# COBConnector.net
KiCad netlist of a schematic drawn in Altium Designer
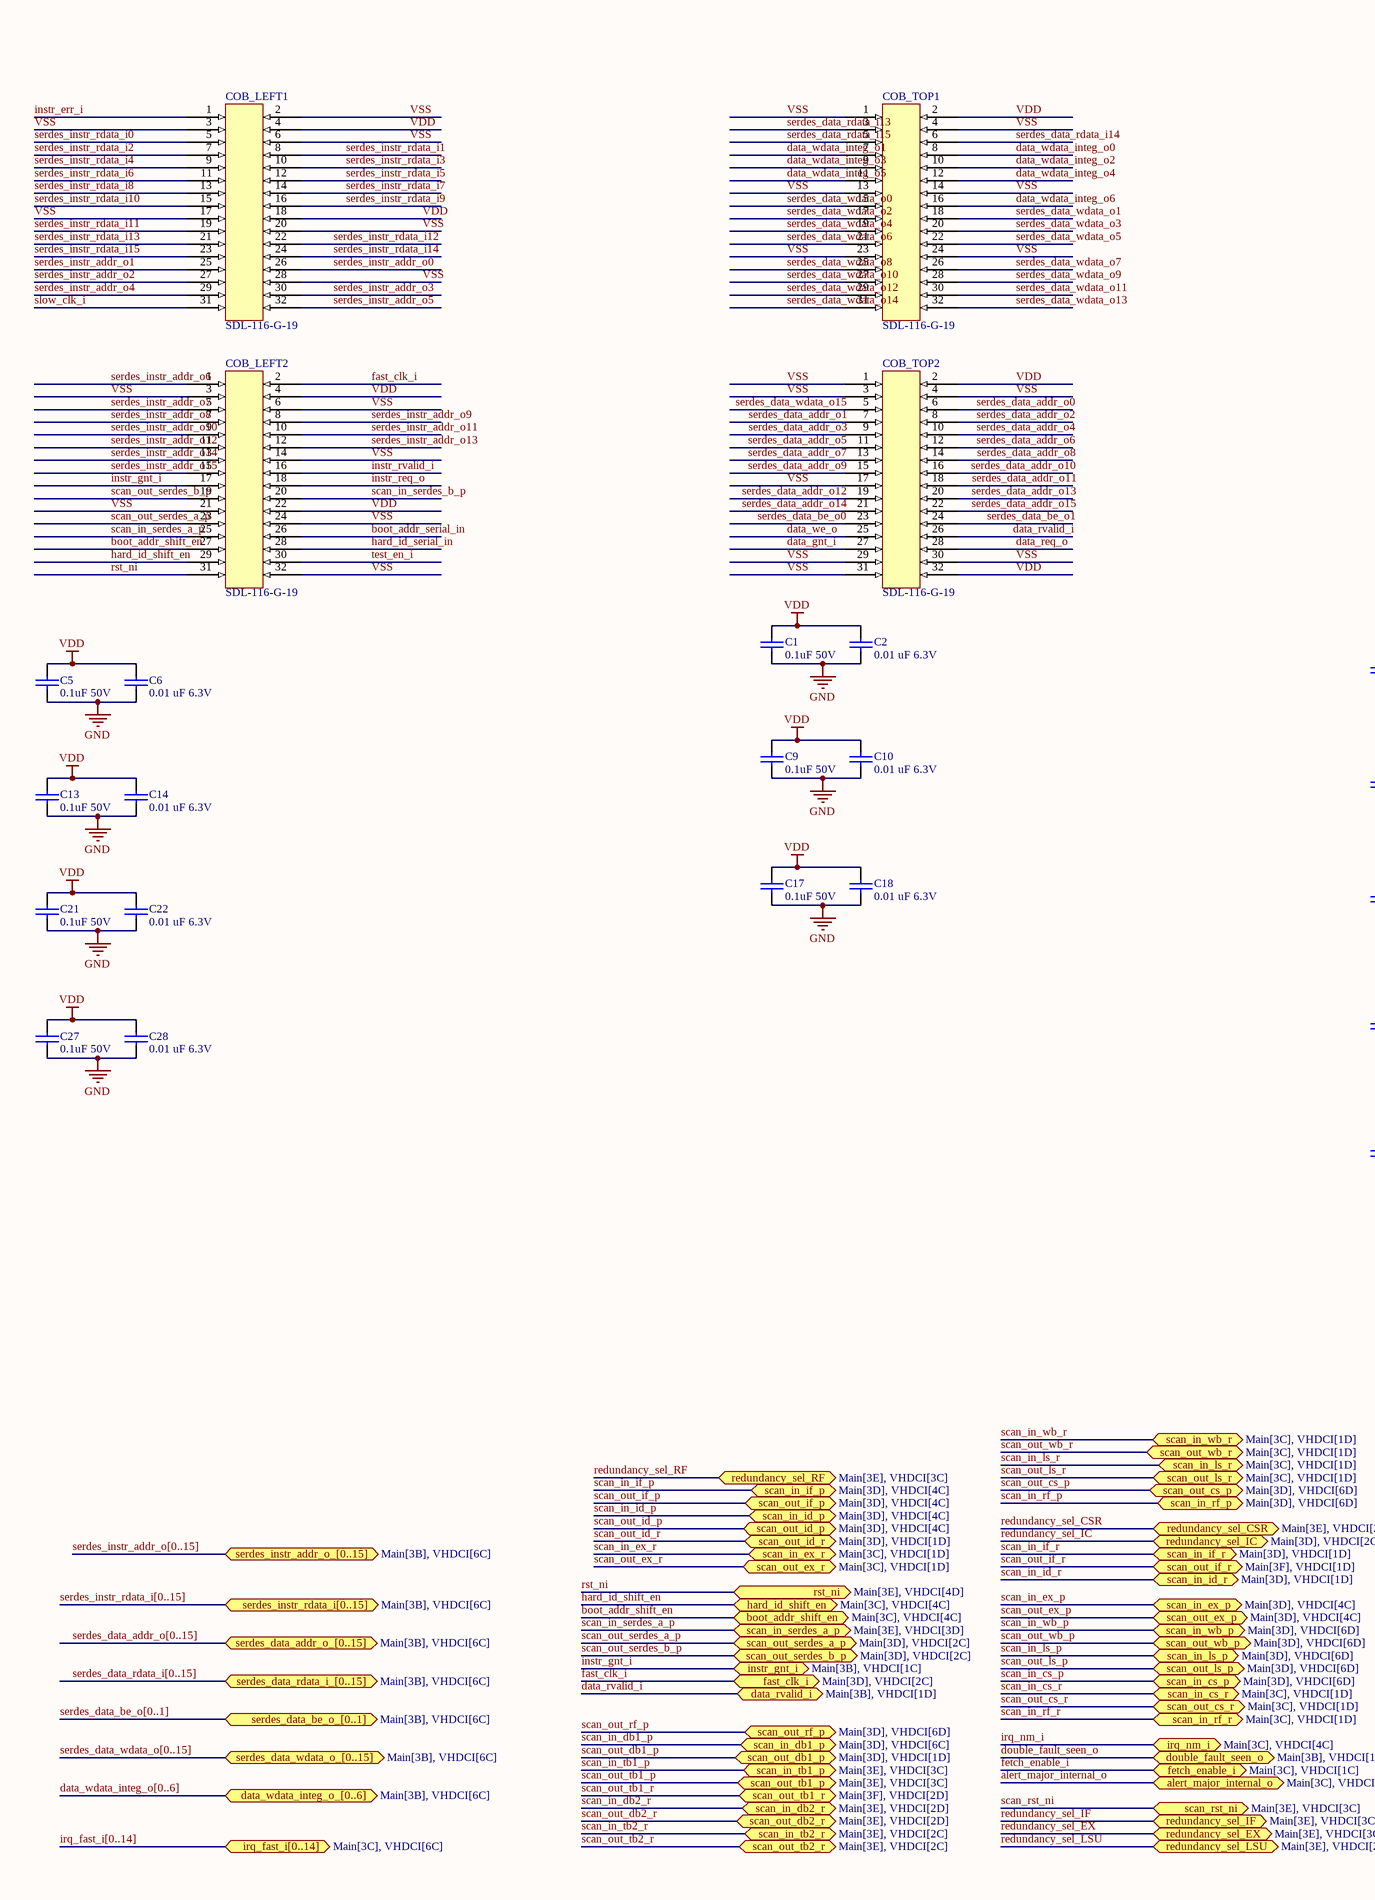
[diagram p0: COBConnector.SchDoc, left]
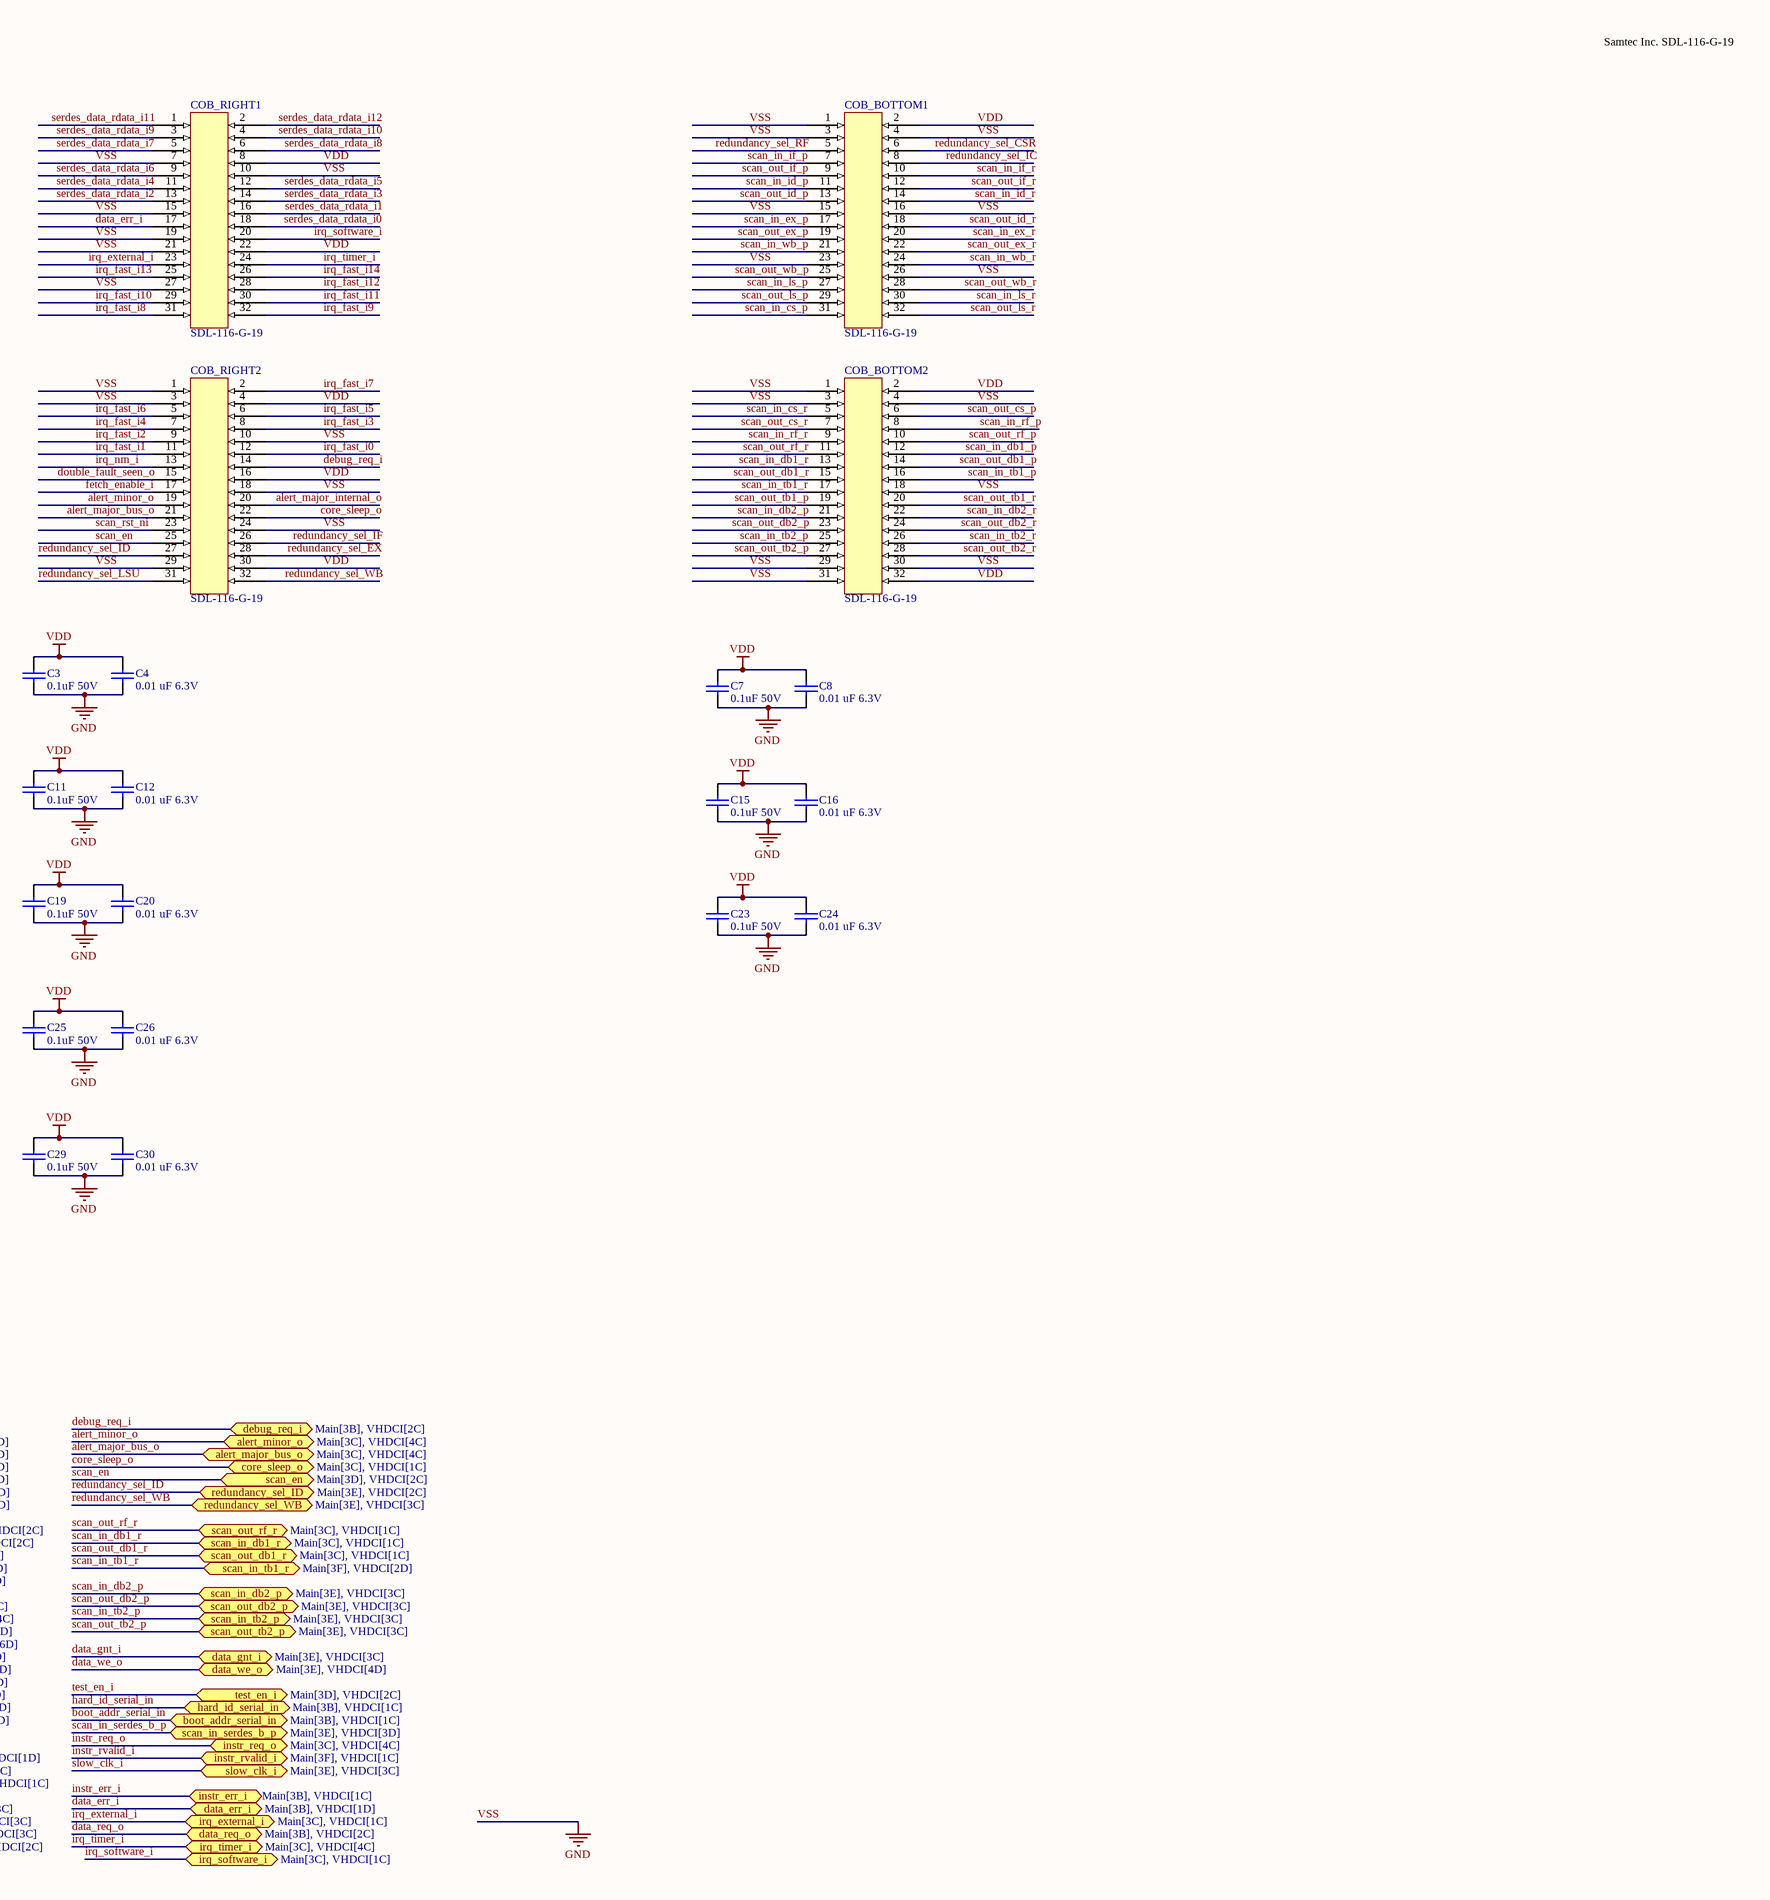
[diagram p1: COBConnector.SchDoc, right]

(export (version "E")
  (design (tool "Eeschema 10.0.6"))
  (components
    (comp (ref "C1")
      (value "0.1uF 50V")
      (footprint "C0603-XXXXXX-XXX")
      (description "0.1 µF ±20% 50V Ceramic Capacitor X7R 0603")
      (libsource (lib "00-100001-001") (part "C0603C104M5RAC7867"))
    )
    (comp (ref "C2")
      (value "0.01 uF 6.3V")
      (footprint "C0603-XXXXXX-XXX")
      (description "Multilayer Ceramic Capacitors MLCC - SMD/SMT 6.3V 0.01uF X7R 0603 20%")
      (libsource (lib "00-100001-001") (part "C0603F103M9RACTU"))
    )
    (comp (ref "C3")
      (value "0.1uF 50V")
      (footprint "C0603-XXXXXX-XXX")
      (description "0.1 µF ±20% 50V Ceramic Capacitor X7R 0603")
      (libsource (lib "00-100001-001") (part "C0603C104M5RAC7867"))
    )
    (comp (ref "C4")
      (value "0.01 uF 6.3V")
      (footprint "C0603-XXXXXX-XXX")
      (description "Multilayer Ceramic Capacitors MLCC - SMD/SMT 6.3V 0.01uF X7R 0603 20%")
      (libsource (lib "00-100001-001") (part "C0603F103M9RACTU"))
    )
    (comp (ref "C5")
      (value "0.1uF 50V")
      (footprint "C0603-XXXXXX-XXX")
      (description "0.1 µF ±20% 50V Ceramic Capacitor X7R 0603")
      (libsource (lib "00-100001-001") (part "C0603C104M5RAC7867"))
    )
    (comp (ref "C6")
      (value "0.01 uF 6.3V")
      (footprint "C0603-XXXXXX-XXX")
      (description "Multilayer Ceramic Capacitors MLCC - SMD/SMT 6.3V 0.01uF X7R 0603 20%")
      (libsource (lib "00-100001-001") (part "C0603F103M9RACTU"))
    )
    (comp (ref "C7")
      (value "0.1uF 50V")
      (footprint "C0603-XXXXXX-XXX")
      (description "0.1 µF ±20% 50V Ceramic Capacitor X7R 0603")
      (libsource (lib "00-100001-001") (part "C0603C104M5RAC7867"))
    )
    (comp (ref "C8")
      (value "0.01 uF 6.3V")
      (footprint "C0603-XXXXXX-XXX")
      (description "Multilayer Ceramic Capacitors MLCC - SMD/SMT 6.3V 0.01uF X7R 0603 20%")
      (libsource (lib "00-100001-001") (part "C0603F103M9RACTU"))
    )
    (comp (ref "C9")
      (value "0.1uF 50V")
      (footprint "C0603-XXXXXX-XXX")
      (description "0.1 µF ±20% 50V Ceramic Capacitor X7R 0603")
      (libsource (lib "00-100001-001") (part "C0603C104M5RAC7867"))
    )
    (comp (ref "C10")
      (value "0.01 uF 6.3V")
      (footprint "C0603-XXXXXX-XXX")
      (description "Multilayer Ceramic Capacitors MLCC - SMD/SMT 6.3V 0.01uF X7R 0603 20%")
      (libsource (lib "00-100001-001") (part "C0603F103M9RACTU"))
    )
    (comp (ref "C11")
      (value "0.1uF 50V")
      (footprint "C0603-XXXXXX-XXX")
      (description "0.1 µF ±20% 50V Ceramic Capacitor X7R 0603")
      (libsource (lib "00-100001-001") (part "C0603C104M5RAC7867"))
    )
    (comp (ref "C12")
      (value "0.01 uF 6.3V")
      (footprint "C0603-XXXXXX-XXX")
      (description "Multilayer Ceramic Capacitors MLCC - SMD/SMT 6.3V 0.01uF X7R 0603 20%")
      (libsource (lib "00-100001-001") (part "C0603F103M9RACTU"))
    )
    (comp (ref "C13")
      (value "0.1uF 50V")
      (footprint "C0603-XXXXXX-XXX")
      (description "0.1 µF ±20% 50V Ceramic Capacitor X7R 0603")
      (libsource (lib "00-100001-001") (part "C0603C104M5RAC7867"))
    )
    (comp (ref "C14")
      (value "0.01 uF 6.3V")
      (footprint "C0603-XXXXXX-XXX")
      (description "Multilayer Ceramic Capacitors MLCC - SMD/SMT 6.3V 0.01uF X7R 0603 20%")
      (libsource (lib "00-100001-001") (part "C0603F103M9RACTU"))
    )
    (comp (ref "C15")
      (value "0.1uF 50V")
      (footprint "C0603-XXXXXX-XXX")
      (description "0.1 µF ±20% 50V Ceramic Capacitor X7R 0603")
      (libsource (lib "00-100001-001") (part "C0603C104M5RAC7867"))
    )
    (comp (ref "C16")
      (value "0.01 uF 6.3V")
      (footprint "C0603-XXXXXX-XXX")
      (description "Multilayer Ceramic Capacitors MLCC - SMD/SMT 6.3V 0.01uF X7R 0603 20%")
      (libsource (lib "00-100001-001") (part "C0603F103M9RACTU"))
    )
    (comp (ref "C17")
      (value "0.1uF 50V")
      (footprint "C0603-XXXXXX-XXX")
      (description "0.1 µF ±20% 50V Ceramic Capacitor X7R 0603")
      (libsource (lib "00-100001-001") (part "C0603C104M5RAC7867"))
    )
    (comp (ref "C18")
      (value "0.01 uF 6.3V")
      (footprint "C0603-XXXXXX-XXX")
      (description "Multilayer Ceramic Capacitors MLCC - SMD/SMT 6.3V 0.01uF X7R 0603 20%")
      (libsource (lib "00-100001-001") (part "C0603F103M9RACTU"))
    )
    (comp (ref "C19")
      (value "0.1uF 50V")
      (footprint "C0603-XXXXXX-XXX")
      (description "0.1 µF ±20% 50V Ceramic Capacitor X7R 0603")
      (libsource (lib "00-100001-001") (part "C0603C104M5RAC7867"))
    )
    (comp (ref "C20")
      (value "0.01 uF 6.3V")
      (footprint "C0603-XXXXXX-XXX")
      (description "Multilayer Ceramic Capacitors MLCC - SMD/SMT 6.3V 0.01uF X7R 0603 20%")
      (libsource (lib "00-100001-001") (part "C0603F103M9RACTU"))
    )
    (comp (ref "C21")
      (value "0.1uF 50V")
      (footprint "C0603-XXXXXX-XXX")
      (description "0.1 µF ±20% 50V Ceramic Capacitor X7R 0603")
      (libsource (lib "00-100001-001") (part "C0603C104M5RAC7867"))
    )
    (comp (ref "C22")
      (value "0.01 uF 6.3V")
      (footprint "C0603-XXXXXX-XXX")
      (description "Multilayer Ceramic Capacitors MLCC - SMD/SMT 6.3V 0.01uF X7R 0603 20%")
      (libsource (lib "00-100001-001") (part "C0603F103M9RACTU"))
    )
    (comp (ref "C23")
      (value "0.1uF 50V")
      (footprint "C0603-XXXXXX-XXX")
      (description "0.1 µF ±20% 50V Ceramic Capacitor X7R 0603")
      (libsource (lib "00-100001-001") (part "C0603C104M5RAC7867"))
    )
    (comp (ref "C24")
      (value "0.01 uF 6.3V")
      (footprint "C0603-XXXXXX-XXX")
      (description "Multilayer Ceramic Capacitors MLCC - SMD/SMT 6.3V 0.01uF X7R 0603 20%")
      (libsource (lib "00-100001-001") (part "C0603F103M9RACTU"))
    )
    (comp (ref "C25")
      (value "0.1uF 50V")
      (footprint "C0603-XXXXXX-XXX")
      (description "0.1 µF ±20% 50V Ceramic Capacitor X7R 0603")
      (libsource (lib "00-100001-001") (part "C0603C104M5RAC7867"))
    )
    (comp (ref "C26")
      (value "0.01 uF 6.3V")
      (footprint "C0603-XXXXXX-XXX")
      (description "Multilayer Ceramic Capacitors MLCC - SMD/SMT 6.3V 0.01uF X7R 0603 20%")
      (libsource (lib "00-100001-001") (part "C0603F103M9RACTU"))
    )
    (comp (ref "C27")
      (value "0.1uF 50V")
      (footprint "C0603-XXXXXX-XXX")
      (description "0.1 µF ±20% 50V Ceramic Capacitor X7R 0603")
      (libsource (lib "00-100001-001") (part "C0603C104M5RAC7867"))
    )
    (comp (ref "C28")
      (value "0.01 uF 6.3V")
      (footprint "C0603-XXXXXX-XXX")
      (description "Multilayer Ceramic Capacitors MLCC - SMD/SMT 6.3V 0.01uF X7R 0603 20%")
      (libsource (lib "00-100001-001") (part "C0603F103M9RACTU"))
    )
    (comp (ref "C29")
      (value "0.1uF 50V")
      (footprint "C0603-XXXXXX-XXX")
      (description "0.1 µF ±20% 50V Ceramic Capacitor X7R 0603")
      (libsource (lib "00-100001-001") (part "C0603C104M5RAC7867"))
    )
    (comp (ref "C30")
      (value "0.01 uF 6.3V")
      (footprint "C0603-XXXXXX-XXX")
      (description "Multilayer Ceramic Capacitors MLCC - SMD/SMT 6.3V 0.01uF X7R 0603 20%")
      (libsource (lib "00-100001-001") (part "C0603F103M9RACTU"))
    )
    (comp (ref "COB_BOTTOM1")
      (value "SDL-116-G-19")
      (footprint "CON32_2X16_TU_DSL_SAI")
      (libsource (lib "00-100001-001") (part "SDL-116-G-19"))
    )
    (comp (ref "COB_BOTTOM2")
      (value "SDL-116-G-19")
      (footprint "CON32_2X16_TU_DSL_SAI")
      (libsource (lib "00-100001-001") (part "SDL-116-G-19"))
    )
    (comp (ref "COB_LEFT1")
      (value "SDL-116-G-19")
      (footprint "CON32_2X16_TU_DSL_SAI")
      (libsource (lib "00-100001-001") (part "SDL-116-G-19"))
    )
    (comp (ref "COB_LEFT2")
      (value "SDL-116-G-19")
      (footprint "CON32_2X16_TU_DSL_SAI")
      (libsource (lib "00-100001-001") (part "SDL-116-G-19"))
    )
    (comp (ref "COB_RIGHT1")
      (value "SDL-116-G-19")
      (footprint "CON32_2X16_TU_DSL_SAI")
      (libsource (lib "00-100001-001") (part "SDL-116-G-19"))
    )
    (comp (ref "COB_RIGHT2")
      (value "SDL-116-G-19")
      (footprint "CON32_2X16_TU_DSL_SAI")
      (libsource (lib "00-100001-001") (part "SDL-116-G-19"))
    )
    (comp (ref "COB_TOP1")
      (value "SDL-116-G-19")
      (footprint "CON32_2X16_TU_DSL_SAI")
      (libsource (lib "00-100001-001") (part "SDL-116-G-19"))
    )
    (comp (ref "COB_TOP2")
      (value "SDL-116-G-19")
      (footprint "CON32_2X16_TU_DSL_SAI")
      (libsource (lib "00-100001-001") (part "SDL-116-G-19"))
    )
  )
  (nets
    (net (code "1") (name "/alert_major_bus_o") (class "Default")
      (node (ref "COB_RIGHT2") (pin "21") (pintype "input"))
    )
    (net (code "2") (name "/alert_major_internal_o") (class "Default")
      (node (ref "COB_RIGHT2") (pin "20") (pintype "input"))
    )
    (net (code "3") (name "/alert_minor_o") (class "Default")
      (node (ref "COB_RIGHT2") (pin "19") (pintype "input"))
    )
    (net (code "4") (name "/boot_addr_serial_in") (class "Default")
      (node (ref "COB_LEFT2") (pin "26") (pintype "input"))
    )
    (net (code "5") (name "/boot_addr_shift_en") (class "Default")
      (node (ref "COB_LEFT2") (pin "27") (pintype "input"))
    )
    (net (code "6") (name "/core_sleep_o") (class "Default")
      (node (ref "COB_RIGHT2") (pin "22") (pintype "input"))
    )
    (net (code "7") (name "/data_err_i") (class "Default")
      (node (ref "COB_RIGHT1") (pin "17") (pintype "input"))
    )
    (net (code "8") (name "/data_gnt_i") (class "Default")
      (node (ref "COB_TOP2") (pin "27") (pintype "input"))
    )
    (net (code "9") (name "/data_req_o") (class "Default")
      (node (ref "COB_TOP2") (pin "28") (pintype "input"))
    )
    (net (code "10") (name "/data_rvalid_i") (class "Default")
      (node (ref "COB_TOP2") (pin "26") (pintype "input"))
    )
    (net (code "11") (name "/data_wdata_integ_o0") (class "Default")
      (node (ref "COB_TOP1") (pin "8") (pintype "input"))
    )
    (net (code "12") (name "/data_wdata_integ_o1") (class "Default")
      (node (ref "COB_TOP1") (pin "7") (pintype "input"))
    )
    (net (code "13") (name "/data_wdata_integ_o2") (class "Default")
      (node (ref "COB_TOP1") (pin "10") (pintype "input"))
    )
    (net (code "14") (name "/data_wdata_integ_o3") (class "Default")
      (node (ref "COB_TOP1") (pin "9") (pintype "input"))
    )
    (net (code "15") (name "/data_wdata_integ_o4") (class "Default")
      (node (ref "COB_TOP1") (pin "12") (pintype "input"))
    )
    (net (code "16") (name "/data_wdata_integ_o5") (class "Default")
      (node (ref "COB_TOP1") (pin "11") (pintype "input"))
    )
    (net (code "17") (name "/data_wdata_integ_o6") (class "Default")
      (node (ref "COB_TOP1") (pin "16") (pintype "input"))
    )
    (net (code "19") (name "/data_we_o") (class "Default")
      (node (ref "COB_TOP2") (pin "25") (pintype "input"))
    )
    (net (code "20") (name "/debug_req_i") (class "Default")
      (node (ref "COB_RIGHT2") (pin "14") (pintype "input"))
    )
    (net (code "21") (name "/double_fault_seen_o") (class "Default")
      (node (ref "COB_RIGHT2") (pin "15") (pintype "input"))
    )
    (net (code "22") (name "/fast_clk_i") (class "Default")
      (node (ref "COB_LEFT2") (pin "2") (pintype "input"))
    )
    (net (code "23") (name "/fetch_enable_i") (class "Default")
      (node (ref "COB_RIGHT2") (pin "17") (pintype "input"))
    )
    (net (code "24") (name "/hard_id_serial_in") (class "Default")
      (node (ref "COB_LEFT2") (pin "28") (pintype "input"))
    )
    (net (code "25") (name "/hard_id_shift_en") (class "Default")
      (node (ref "COB_LEFT2") (pin "29") (pintype "input"))
    )
    (net (code "26") (name "/instr_err_i") (class "Default")
      (node (ref "COB_LEFT1") (pin "1") (pintype "input"))
    )
    (net (code "27") (name "/instr_gnt_i") (class "Default")
      (node (ref "COB_LEFT2") (pin "17") (pintype "input"))
    )
    (net (code "28") (name "/instr_req_o") (class "Default")
      (node (ref "COB_LEFT2") (pin "18") (pintype "input"))
    )
    (net (code "29") (name "/instr_rvalid_i") (class "Default")
      (node (ref "COB_LEFT2") (pin "16") (pintype "input"))
    )
    (net (code "30") (name "/irq_external_i") (class "Default")
      (node (ref "COB_RIGHT1") (pin "23") (pintype "input"))
    )
    (net (code "31") (name "/irq_fast_i0") (class "Default")
      (node (ref "COB_RIGHT2") (pin "12") (pintype "input"))
    )
    (net (code "32") (name "/irq_fast_i1") (class "Default")
      (node (ref "COB_RIGHT2") (pin "11") (pintype "input"))
    )
    (net (code "33") (name "/irq_fast_i2") (class "Default")
      (node (ref "COB_RIGHT2") (pin "9") (pintype "input"))
    )
    (net (code "34") (name "/irq_fast_i3") (class "Default")
      (node (ref "COB_RIGHT2") (pin "8") (pintype "input"))
    )
    (net (code "35") (name "/irq_fast_i4") (class "Default")
      (node (ref "COB_RIGHT2") (pin "7") (pintype "input"))
    )
    (net (code "36") (name "/irq_fast_i5") (class "Default")
      (node (ref "COB_RIGHT2") (pin "6") (pintype "input"))
    )
    (net (code "37") (name "/irq_fast_i6") (class "Default")
      (node (ref "COB_RIGHT2") (pin "5") (pintype "input"))
    )
    (net (code "38") (name "/irq_fast_i7") (class "Default")
      (node (ref "COB_RIGHT2") (pin "2") (pintype "input"))
    )
    (net (code "39") (name "/irq_fast_i8") (class "Default")
      (node (ref "COB_RIGHT1") (pin "31") (pintype "input"))
    )
    (net (code "40") (name "/irq_fast_i9") (class "Default")
      (node (ref "COB_RIGHT1") (pin "32") (pintype "input"))
    )
    (net (code "41") (name "/irq_fast_i10") (class "Default")
      (node (ref "COB_RIGHT1") (pin "29") (pintype "input"))
    )
    (net (code "42") (name "/irq_fast_i11") (class "Default")
      (node (ref "COB_RIGHT1") (pin "30") (pintype "input"))
    )
    (net (code "43") (name "/irq_fast_i12") (class "Default")
      (node (ref "COB_RIGHT1") (pin "28") (pintype "input"))
    )
    (net (code "44") (name "/irq_fast_i13") (class "Default")
      (node (ref "COB_RIGHT1") (pin "25") (pintype "input"))
    )
    (net (code "45") (name "/irq_fast_i14") (class "Default")
      (node (ref "COB_RIGHT1") (pin "26") (pintype "input"))
    )
    (net (code "47") (name "/irq_nm_i") (class "Default")
      (node (ref "COB_RIGHT2") (pin "13") (pintype "input"))
    )
    (net (code "48") (name "/irq_software_i") (class "Default")
      (node (ref "COB_RIGHT1") (pin "20") (pintype "input"))
    )
    (net (code "49") (name "/irq_timer_i") (class "Default")
      (node (ref "COB_RIGHT1") (pin "24") (pintype "input"))
    )
    (net (code "50") (name "/redundancy_sel_CSR") (class "Default")
      (node (ref "COB_BOTTOM1") (pin "6") (pintype "input"))
    )
    (net (code "51") (name "/redundancy_sel_EX") (class "Default")
      (node (ref "COB_RIGHT2") (pin "28") (pintype "input"))
    )
    (net (code "52") (name "/redundancy_sel_IC") (class "Default")
      (node (ref "COB_BOTTOM1") (pin "8") (pintype "input"))
    )
    (net (code "53") (name "/redundancy_sel_ID") (class "Default")
      (node (ref "COB_RIGHT2") (pin "27") (pintype "input"))
    )
    (net (code "54") (name "/redundancy_sel_IF") (class "Default")
      (node (ref "COB_RIGHT2") (pin "26") (pintype "input"))
    )
    (net (code "55") (name "/redundancy_sel_LSU") (class "Default")
      (node (ref "COB_RIGHT2") (pin "31") (pintype "input"))
    )
    (net (code "56") (name "/redundancy_sel_RF") (class "Default")
      (node (ref "COB_BOTTOM1") (pin "5") (pintype "input"))
    )
    (net (code "57") (name "/redundancy_sel_WB") (class "Default")
      (node (ref "COB_RIGHT2") (pin "32") (pintype "input"))
    )
    (net (code "58") (name "/rst_ni") (class "Default") (node (ref "COB_LEFT2") (pin "31") (pintype "input")))
    (net (code "59") (name "/scan_en") (class "Default")
      (node (ref "COB_RIGHT2") (pin "25") (pintype "input"))
    )
    (net (code "60") (name "/scan_in_cs_p") (class "Default")
      (node (ref "COB_BOTTOM1") (pin "31") (pintype "input"))
    )
    (net (code "61") (name "/scan_in_cs_r") (class "Default")
      (node (ref "COB_BOTTOM2") (pin "5") (pintype "input"))
    )
    (net (code "62") (name "/scan_in_db1_p") (class "Default")
      (node (ref "COB_BOTTOM2") (pin "12") (pintype "input"))
    )
    (net (code "63") (name "/scan_in_db1_r") (class "Default")
      (node (ref "COB_BOTTOM2") (pin "13") (pintype "input"))
    )
    (net (code "64") (name "/scan_in_db2_p") (class "Default")
      (node (ref "COB_BOTTOM2") (pin "21") (pintype "input"))
    )
    (net (code "65") (name "/scan_in_db2_r") (class "Default")
      (node (ref "COB_BOTTOM2") (pin "22") (pintype "input"))
    )
    (net (code "66") (name "/scan_in_ex_p") (class "Default")
      (node (ref "COB_BOTTOM1") (pin "17") (pintype "input"))
    )
    (net (code "67") (name "/scan_in_ex_r") (class "Default")
      (node (ref "COB_BOTTOM1") (pin "20") (pintype "input"))
    )
    (net (code "68") (name "/scan_in_id_p") (class "Default")
      (node (ref "COB_BOTTOM1") (pin "11") (pintype "input"))
    )
    (net (code "69") (name "/scan_in_id_r") (class "Default")
      (node (ref "COB_BOTTOM1") (pin "14") (pintype "input"))
    )
    (net (code "70") (name "/scan_in_if_p") (class "Default")
      (node (ref "COB_BOTTOM1") (pin "7") (pintype "input"))
    )
    (net (code "71") (name "/scan_in_if_r") (class "Default")
      (node (ref "COB_BOTTOM1") (pin "10") (pintype "input"))
    )
    (net (code "72") (name "/scan_in_ls_p") (class "Default")
      (node (ref "COB_BOTTOM1") (pin "27") (pintype "input"))
    )
    (net (code "73") (name "/scan_in_ls_r") (class "Default")
      (node (ref "COB_BOTTOM1") (pin "30") (pintype "input"))
    )
    (net (code "74") (name "/scan_in_rf_p") (class "Default")
      (node (ref "COB_BOTTOM2") (pin "8") (pintype "input"))
    )
    (net (code "75") (name "/scan_in_rf_r") (class "Default")
      (node (ref "COB_BOTTOM2") (pin "9") (pintype "input"))
    )
    (net (code "76") (name "/scan_in_serdes_a_p") (class "Default")
      (node (ref "COB_LEFT2") (pin "25") (pintype "input"))
    )
    (net (code "77") (name "/scan_in_serdes_b_p") (class "Default")
      (node (ref "COB_LEFT2") (pin "20") (pintype "input"))
    )
    (net (code "78") (name "/scan_in_tb1_p") (class "Default")
      (node (ref "COB_BOTTOM2") (pin "16") (pintype "input"))
    )
    (net (code "79") (name "/scan_in_tb1_r") (class "Default")
      (node (ref "COB_BOTTOM2") (pin "17") (pintype "input"))
    )
    (net (code "80") (name "/scan_in_tb2_p") (class "Default")
      (node (ref "COB_BOTTOM2") (pin "25") (pintype "input"))
    )
    (net (code "81") (name "/scan_in_tb2_r") (class "Default")
      (node (ref "COB_BOTTOM2") (pin "26") (pintype "input"))
    )
    (net (code "82") (name "/scan_in_wb_p") (class "Default")
      (node (ref "COB_BOTTOM1") (pin "21") (pintype "input"))
    )
    (net (code "83") (name "/scan_in_wb_r") (class "Default")
      (node (ref "COB_BOTTOM1") (pin "24") (pintype "input"))
    )
    (net (code "84") (name "/scan_out_cs_p") (class "Default")
      (node (ref "COB_BOTTOM2") (pin "6") (pintype "input"))
    )
    (net (code "85") (name "/scan_out_cs_r") (class "Default")
      (node (ref "COB_BOTTOM2") (pin "7") (pintype "input"))
    )
    (net (code "86") (name "/scan_out_db1_p") (class "Default")
      (node (ref "COB_BOTTOM2") (pin "14") (pintype "input"))
    )
    (net (code "87") (name "/scan_out_db1_r") (class "Default")
      (node (ref "COB_BOTTOM2") (pin "15") (pintype "input"))
    )
    (net (code "88") (name "/scan_out_db2_p") (class "Default")
      (node (ref "COB_BOTTOM2") (pin "23") (pintype "input"))
    )
    (net (code "89") (name "/scan_out_db2_r") (class "Default")
      (node (ref "COB_BOTTOM2") (pin "24") (pintype "input"))
    )
    (net (code "90") (name "/scan_out_ex_p") (class "Default")
      (node (ref "COB_BOTTOM1") (pin "19") (pintype "input"))
    )
    (net (code "91") (name "/scan_out_ex_r") (class "Default")
      (node (ref "COB_BOTTOM1") (pin "22") (pintype "input"))
    )
    (net (code "92") (name "/scan_out_id_p") (class "Default")
      (node (ref "COB_BOTTOM1") (pin "13") (pintype "input"))
    )
    (net (code "93") (name "/scan_out_id_r") (class "Default")
      (node (ref "COB_BOTTOM1") (pin "18") (pintype "input"))
    )
    (net (code "94") (name "/scan_out_if_p") (class "Default")
      (node (ref "COB_BOTTOM1") (pin "9") (pintype "input"))
    )
    (net (code "95") (name "/scan_out_if_r") (class "Default")
      (node (ref "COB_BOTTOM1") (pin "12") (pintype "input"))
    )
    (net (code "96") (name "/scan_out_ls_p") (class "Default")
      (node (ref "COB_BOTTOM1") (pin "29") (pintype "input"))
    )
    (net (code "97") (name "/scan_out_ls_r") (class "Default")
      (node (ref "COB_BOTTOM1") (pin "32") (pintype "input"))
    )
    (net (code "98") (name "/scan_out_rf_p") (class "Default")
      (node (ref "COB_BOTTOM2") (pin "10") (pintype "input"))
    )
    (net (code "99") (name "/scan_out_rf_r") (class "Default")
      (node (ref "COB_BOTTOM2") (pin "11") (pintype "input"))
    )
    (net (code "100") (name "/scan_out_serdes_a_p") (class "Default")
      (node (ref "COB_LEFT2") (pin "23") (pintype "input"))
    )
    (net (code "101") (name "/scan_out_serdes_b_p") (class "Default")
      (node (ref "COB_LEFT2") (pin "19") (pintype "input"))
    )
    (net (code "102") (name "/scan_out_tb1_p") (class "Default")
      (node (ref "COB_BOTTOM2") (pin "19") (pintype "input"))
    )
    (net (code "103") (name "/scan_out_tb1_r") (class "Default")
      (node (ref "COB_BOTTOM2") (pin "20") (pintype "input"))
    )
    (net (code "104") (name "/scan_out_tb2_p") (class "Default")
      (node (ref "COB_BOTTOM2") (pin "27") (pintype "input"))
    )
    (net (code "105") (name "/scan_out_tb2_r") (class "Default")
      (node (ref "COB_BOTTOM2") (pin "28") (pintype "input"))
    )
    (net (code "106") (name "/scan_out_wb_p") (class "Default")
      (node (ref "COB_BOTTOM1") (pin "25") (pintype "input"))
    )
    (net (code "107") (name "/scan_out_wb_r") (class "Default")
      (node (ref "COB_BOTTOM1") (pin "28") (pintype "input"))
    )
    (net (code "108") (name "/scan_rst_ni") (class "Default")
      (node (ref "COB_RIGHT2") (pin "23") (pintype "input"))
    )
    (net (code "109") (name "/serdes_data_addr_o0") (class "Default")
      (node (ref "COB_TOP2") (pin "6") (pintype "input"))
    )
    (net (code "110") (name "/serdes_data_addr_o1") (class "Default")
      (node (ref "COB_TOP2") (pin "7") (pintype "input"))
    )
    (net (code "111") (name "/serdes_data_addr_o2") (class "Default")
      (node (ref "COB_TOP2") (pin "8") (pintype "input"))
    )
    (net (code "112") (name "/serdes_data_addr_o3") (class "Default")
      (node (ref "COB_TOP2") (pin "9") (pintype "input"))
    )
    (net (code "113") (name "/serdes_data_addr_o4") (class "Default")
      (node (ref "COB_TOP2") (pin "10") (pintype "input"))
    )
    (net (code "114") (name "/serdes_data_addr_o5") (class "Default")
      (node (ref "COB_TOP2") (pin "11") (pintype "input"))
    )
    (net (code "115") (name "/serdes_data_addr_o6") (class "Default")
      (node (ref "COB_TOP2") (pin "12") (pintype "input"))
    )
    (net (code "116") (name "/serdes_data_addr_o7") (class "Default")
      (node (ref "COB_TOP2") (pin "13") (pintype "input"))
    )
    (net (code "117") (name "/serdes_data_addr_o8") (class "Default")
      (node (ref "COB_TOP2") (pin "14") (pintype "input"))
    )
    (net (code "118") (name "/serdes_data_addr_o9") (class "Default")
      (node (ref "COB_TOP2") (pin "15") (pintype "input"))
    )
    (net (code "119") (name "/serdes_data_addr_o10") (class "Default")
      (node (ref "COB_TOP2") (pin "16") (pintype "input"))
    )
    (net (code "120") (name "/serdes_data_addr_o11") (class "Default")
      (node (ref "COB_TOP2") (pin "18") (pintype "input"))
    )
    (net (code "121") (name "/serdes_data_addr_o12") (class "Default")
      (node (ref "COB_TOP2") (pin "19") (pintype "input"))
    )
    (net (code "122") (name "/serdes_data_addr_o13") (class "Default")
      (node (ref "COB_TOP2") (pin "20") (pintype "input"))
    )
    (net (code "123") (name "/serdes_data_addr_o14") (class "Default")
      (node (ref "COB_TOP2") (pin "21") (pintype "input"))
    )
    (net (code "124") (name "/serdes_data_addr_o15") (class "Default")
      (node (ref "COB_TOP2") (pin "22") (pintype "input"))
    )
    (net (code "126") (name "/serdes_data_be_o0") (class "Default")
      (node (ref "COB_TOP2") (pin "23") (pintype "input"))
    )
    (net (code "127") (name "/serdes_data_be_o1") (class "Default")
      (node (ref "COB_TOP2") (pin "24") (pintype "input"))
    )
    (net (code "129") (name "/serdes_data_rdata_i0") (class "Default")
      (node (ref "COB_RIGHT1") (pin "18") (pintype "input"))
    )
    (net (code "130") (name "/serdes_data_rdata_i1") (class "Default")
      (node (ref "COB_RIGHT1") (pin "16") (pintype "input"))
    )
    (net (code "131") (name "/serdes_data_rdata_i2") (class "Default")
      (node (ref "COB_RIGHT1") (pin "13") (pintype "input"))
    )
    (net (code "132") (name "/serdes_data_rdata_i3") (class "Default")
      (node (ref "COB_RIGHT1") (pin "14") (pintype "input"))
    )
    (net (code "133") (name "/serdes_data_rdata_i4") (class "Default")
      (node (ref "COB_RIGHT1") (pin "11") (pintype "input"))
    )
    (net (code "134") (name "/serdes_data_rdata_i5") (class "Default")
      (node (ref "COB_RIGHT1") (pin "12") (pintype "input"))
    )
    (net (code "135") (name "/serdes_data_rdata_i6") (class "Default")
      (node (ref "COB_RIGHT1") (pin "9") (pintype "input"))
    )
    (net (code "136") (name "/serdes_data_rdata_i7") (class "Default")
      (node (ref "COB_RIGHT1") (pin "5") (pintype "input"))
    )
    (net (code "137") (name "/serdes_data_rdata_i8") (class "Default")
      (node (ref "COB_RIGHT1") (pin "6") (pintype "input"))
    )
    (net (code "138") (name "/serdes_data_rdata_i9") (class "Default")
      (node (ref "COB_RIGHT1") (pin "3") (pintype "input"))
    )
    (net (code "139") (name "/serdes_data_rdata_i10") (class "Default")
      (node (ref "COB_RIGHT1") (pin "4") (pintype "input"))
    )
    (net (code "140") (name "/serdes_data_rdata_i11") (class "Default")
      (node (ref "COB_RIGHT1") (pin "1") (pintype "input"))
    )
    (net (code "141") (name "/serdes_data_rdata_i12") (class "Default")
      (node (ref "COB_RIGHT1") (pin "2") (pintype "input"))
    )
    (net (code "142") (name "/serdes_data_rdata_i13") (class "Default")
      (node (ref "COB_TOP1") (pin "3") (pintype "input"))
    )
    (net (code "143") (name "/serdes_data_rdata_i14") (class "Default")
      (node (ref "COB_TOP1") (pin "6") (pintype "input"))
    )
    (net (code "144") (name "/serdes_data_rdata_i15") (class "Default")
      (node (ref "COB_TOP1") (pin "5") (pintype "input"))
    )
    (net (code "146") (name "/serdes_data_wdata_o0") (class "Default")
      (node (ref "COB_TOP1") (pin "15") (pintype "input"))
    )
    (net (code "147") (name "/serdes_data_wdata_o1") (class "Default")
      (node (ref "COB_TOP1") (pin "18") (pintype "input"))
    )
    (net (code "148") (name "/serdes_data_wdata_o2") (class "Default")
      (node (ref "COB_TOP1") (pin "17") (pintype "input"))
    )
    (net (code "149") (name "/serdes_data_wdata_o3") (class "Default")
      (node (ref "COB_TOP1") (pin "20") (pintype "input"))
    )
    (net (code "150") (name "/serdes_data_wdata_o4") (class "Default")
      (node (ref "COB_TOP1") (pin "19") (pintype "input"))
    )
    (net (code "151") (name "/serdes_data_wdata_o5") (class "Default")
      (node (ref "COB_TOP1") (pin "22") (pintype "input"))
    )
    (net (code "152") (name "/serdes_data_wdata_o6") (class "Default")
      (node (ref "COB_TOP1") (pin "21") (pintype "input"))
    )
    (net (code "153") (name "/serdes_data_wdata_o7") (class "Default")
      (node (ref "COB_TOP1") (pin "26") (pintype "input"))
    )
    (net (code "154") (name "/serdes_data_wdata_o8") (class "Default")
      (node (ref "COB_TOP1") (pin "25") (pintype "input"))
    )
    (net (code "155") (name "/serdes_data_wdata_o9") (class "Default")
      (node (ref "COB_TOP1") (pin "28") (pintype "input"))
    )
    (net (code "156") (name "/serdes_data_wdata_o10") (class "Default")
      (node (ref "COB_TOP1") (pin "27") (pintype "input"))
    )
    (net (code "157") (name "/serdes_data_wdata_o11") (class "Default")
      (node (ref "COB_TOP1") (pin "30") (pintype "input"))
    )
    (net (code "158") (name "/serdes_data_wdata_o12") (class "Default")
      (node (ref "COB_TOP1") (pin "29") (pintype "input"))
    )
    (net (code "159") (name "/serdes_data_wdata_o13") (class "Default")
      (node (ref "COB_TOP1") (pin "32") (pintype "input"))
    )
    (net (code "160") (name "/serdes_data_wdata_o14") (class "Default")
      (node (ref "COB_TOP1") (pin "31") (pintype "input"))
    )
    (net (code "161") (name "/serdes_data_wdata_o15") (class "Default")
      (node (ref "COB_TOP2") (pin "5") (pintype "input"))
    )
    (net (code "163") (name "/serdes_instr_addr_o0") (class "Default")
      (node (ref "COB_LEFT1") (pin "26") (pintype "input"))
    )
    (net (code "164") (name "/serdes_instr_addr_o1") (class "Default")
      (node (ref "COB_LEFT1") (pin "25") (pintype "input"))
    )
    (net (code "165") (name "/serdes_instr_addr_o2") (class "Default")
      (node (ref "COB_LEFT1") (pin "27") (pintype "input"))
    )
    (net (code "166") (name "/serdes_instr_addr_o3") (class "Default")
      (node (ref "COB_LEFT1") (pin "30") (pintype "input"))
    )
    (net (code "167") (name "/serdes_instr_addr_o4") (class "Default")
      (node (ref "COB_LEFT1") (pin "29") (pintype "input"))
    )
    (net (code "168") (name "/serdes_instr_addr_o5") (class "Default")
      (node (ref "COB_LEFT1") (pin "32") (pintype "input"))
    )
    (net (code "169") (name "/serdes_instr_addr_o6") (class "Default")
      (node (ref "COB_LEFT2") (pin "1") (pintype "input"))
    )
    (net (code "170") (name "/serdes_instr_addr_o7") (class "Default")
      (node (ref "COB_LEFT2") (pin "5") (pintype "input"))
    )
    (net (code "171") (name "/serdes_instr_addr_o8") (class "Default")
      (node (ref "COB_LEFT2") (pin "7") (pintype "input"))
    )
    (net (code "172") (name "/serdes_instr_addr_o9") (class "Default")
      (node (ref "COB_LEFT2") (pin "8") (pintype "input"))
    )
    (net (code "173") (name "/serdes_instr_addr_o10") (class "Default")
      (node (ref "COB_LEFT2") (pin "9") (pintype "input"))
    )
    (net (code "174") (name "/serdes_instr_addr_o11") (class "Default")
      (node (ref "COB_LEFT2") (pin "10") (pintype "input"))
    )
    (net (code "175") (name "/serdes_instr_addr_o12") (class "Default")
      (node (ref "COB_LEFT2") (pin "11") (pintype "input"))
    )
    (net (code "176") (name "/serdes_instr_addr_o13") (class "Default")
      (node (ref "COB_LEFT2") (pin "12") (pintype "input"))
    )
    (net (code "177") (name "/serdes_instr_addr_o14") (class "Default")
      (node (ref "COB_LEFT2") (pin "13") (pintype "input"))
    )
    (net (code "178") (name "/serdes_instr_addr_o15") (class "Default")
      (node (ref "COB_LEFT2") (pin "15") (pintype "input"))
    )
    (net (code "180") (name "/serdes_instr_rdata_i0") (class "Default")
      (node (ref "COB_LEFT1") (pin "5") (pintype "input"))
    )
    (net (code "181") (name "/serdes_instr_rdata_i1") (class "Default")
      (node (ref "COB_LEFT1") (pin "8") (pintype "input"))
    )
    (net (code "182") (name "/serdes_instr_rdata_i2") (class "Default")
      (node (ref "COB_LEFT1") (pin "7") (pintype "input"))
    )
    (net (code "183") (name "/serdes_instr_rdata_i3") (class "Default")
      (node (ref "COB_LEFT1") (pin "10") (pintype "input"))
    )
    (net (code "184") (name "/serdes_instr_rdata_i4") (class "Default")
      (node (ref "COB_LEFT1") (pin "9") (pintype "input"))
    )
    (net (code "185") (name "/serdes_instr_rdata_i5") (class "Default")
      (node (ref "COB_LEFT1") (pin "12") (pintype "input"))
    )
    (net (code "186") (name "/serdes_instr_rdata_i6") (class "Default")
      (node (ref "COB_LEFT1") (pin "11") (pintype "input"))
    )
    (net (code "187") (name "/serdes_instr_rdata_i7") (class "Default")
      (node (ref "COB_LEFT1") (pin "14") (pintype "input"))
    )
    (net (code "188") (name "/serdes_instr_rdata_i8") (class "Default")
      (node (ref "COB_LEFT1") (pin "13") (pintype "input"))
    )
    (net (code "189") (name "/serdes_instr_rdata_i9") (class "Default")
      (node (ref "COB_LEFT1") (pin "16") (pintype "input"))
    )
    (net (code "190") (name "/serdes_instr_rdata_i10") (class "Default")
      (node (ref "COB_LEFT1") (pin "15") (pintype "input"))
    )
    (net (code "191") (name "/serdes_instr_rdata_i11") (class "Default")
      (node (ref "COB_LEFT1") (pin "19") (pintype "input"))
    )
    (net (code "192") (name "/serdes_instr_rdata_i12") (class "Default")
      (node (ref "COB_LEFT1") (pin "22") (pintype "input"))
    )
    (net (code "193") (name "/serdes_instr_rdata_i13") (class "Default")
      (node (ref "COB_LEFT1") (pin "21") (pintype "input"))
    )
    (net (code "194") (name "/serdes_instr_rdata_i14") (class "Default")
      (node (ref "COB_LEFT1") (pin "24") (pintype "input"))
    )
    (net (code "195") (name "/serdes_instr_rdata_i15") (class "Default")
      (node (ref "COB_LEFT1") (pin "23") (pintype "input"))
    )
    (net (code "197") (name "/slow_clk_i") (class "Default")
      (node (ref "COB_LEFT1") (pin "31") (pintype "input"))
    )
    (net (code "198") (name "/test_en_i") (class "Default")
      (node (ref "COB_LEFT2") (pin "30") (pintype "input"))
    )
    (net (code "199") (name "GND") (class "Default")
      (node (ref "C1") (pin "2") (pinfunction "2_2") (pintype "passive"))
      (node (ref "C10") (pin "2") (pinfunction "2_2") (pintype "passive"))
      (node (ref "C11") (pin "2") (pinfunction "2_2") (pintype "passive"))
      (node (ref "C12") (pin "2") (pinfunction "2_2") (pintype "passive"))
      (node (ref "C13") (pin "2") (pinfunction "2_2") (pintype "passive"))
      (node (ref "C14") (pin "2") (pinfunction "2_2") (pintype "passive"))
      (node (ref "C15") (pin "2") (pinfunction "2_2") (pintype "passive"))
      (node (ref "C16") (pin "2") (pinfunction "2_2") (pintype "passive"))
      (node (ref "C17") (pin "2") (pinfunction "2_2") (pintype "passive"))
      (node (ref "C18") (pin "2") (pinfunction "2_2") (pintype "passive"))
      (node (ref "C19") (pin "2") (pinfunction "2_2") (pintype "passive"))
      (node (ref "C2") (pin "2") (pinfunction "2_2") (pintype "passive"))
      (node (ref "C20") (pin "2") (pinfunction "2_2") (pintype "passive"))
      (node (ref "C21") (pin "2") (pinfunction "2_2") (pintype "passive"))
      (node (ref "C22") (pin "2") (pinfunction "2_2") (pintype "passive"))
      (node (ref "C23") (pin "2") (pinfunction "2_2") (pintype "passive"))
      (node (ref "C24") (pin "2") (pinfunction "2_2") (pintype "passive"))
      (node (ref "C25") (pin "2") (pinfunction "2_2") (pintype "passive"))
      (node (ref "C26") (pin "2") (pinfunction "2_2") (pintype "passive"))
      (node (ref "C27") (pin "2") (pinfunction "2_2") (pintype "passive"))
      (node (ref "C28") (pin "2") (pinfunction "2_2") (pintype "passive"))
      (node (ref "C29") (pin "2") (pinfunction "2_2") (pintype "passive"))
      (node (ref "C3") (pin "2") (pinfunction "2_2") (pintype "passive"))
      (node (ref "C30") (pin "2") (pinfunction "2_2") (pintype "passive"))
      (node (ref "C4") (pin "2") (pinfunction "2_2") (pintype "passive"))
      (node (ref "C5") (pin "2") (pinfunction "2_2") (pintype "passive"))
      (node (ref "C6") (pin "2") (pinfunction "2_2") (pintype "passive"))
      (node (ref "C7") (pin "2") (pinfunction "2_2") (pintype "passive"))
      (node (ref "C8") (pin "2") (pinfunction "2_2") (pintype "passive"))
      (node (ref "C9") (pin "2") (pinfunction "2_2") (pintype "passive"))
      (node (ref "COB_BOTTOM1") (pin "1") (pintype "input"))
      (node (ref "COB_BOTTOM1") (pin "15") (pintype "input"))
      (node (ref "COB_BOTTOM1") (pin "16") (pintype "input"))
      (node (ref "COB_BOTTOM1") (pin "23") (pintype "input"))
      (node (ref "COB_BOTTOM1") (pin "26") (pintype "input"))
      (node (ref "COB_BOTTOM1") (pin "3") (pintype "input"))
      (node (ref "COB_BOTTOM1") (pin "4") (pintype "input"))
      (node (ref "COB_BOTTOM2") (pin "1") (pintype "input"))
      (node (ref "COB_BOTTOM2") (pin "18") (pintype "input"))
      (node (ref "COB_BOTTOM2") (pin "29") (pintype "input"))
      (node (ref "COB_BOTTOM2") (pin "3") (pintype "input"))
      (node (ref "COB_BOTTOM2") (pin "30") (pintype "input"))
      (node (ref "COB_BOTTOM2") (pin "31") (pintype "input"))
      (node (ref "COB_BOTTOM2") (pin "4") (pintype "input"))
      (node (ref "COB_LEFT1") (pin "17") (pintype "input"))
      (node (ref "COB_LEFT1") (pin "2") (pintype "input"))
      (node (ref "COB_LEFT1") (pin "20") (pintype "input"))
      (node (ref "COB_LEFT1") (pin "28") (pintype "input"))
      (node (ref "COB_LEFT1") (pin "3") (pintype "input"))
      (node (ref "COB_LEFT1") (pin "6") (pintype "input"))
      (node (ref "COB_LEFT2") (pin "14") (pintype "input"))
      (node (ref "COB_LEFT2") (pin "21") (pintype "input"))
      (node (ref "COB_LEFT2") (pin "24") (pintype "input"))
      (node (ref "COB_LEFT2") (pin "3") (pintype "input"))
      (node (ref "COB_LEFT2") (pin "32") (pintype "input"))
      (node (ref "COB_LEFT2") (pin "6") (pintype "input"))
      (node (ref "COB_RIGHT1") (pin "10") (pintype "input"))
      (node (ref "COB_RIGHT1") (pin "15") (pintype "input"))
      (node (ref "COB_RIGHT1") (pin "19") (pintype "input"))
      (node (ref "COB_RIGHT1") (pin "21") (pintype "input"))
      (node (ref "COB_RIGHT1") (pin "27") (pintype "input"))
      (node (ref "COB_RIGHT1") (pin "7") (pintype "input"))
      (node (ref "COB_RIGHT2") (pin "1") (pintype "input"))
      (node (ref "COB_RIGHT2") (pin "10") (pintype "input"))
      (node (ref "COB_RIGHT2") (pin "18") (pintype "input"))
      (node (ref "COB_RIGHT2") (pin "24") (pintype "input"))
      (node (ref "COB_RIGHT2") (pin "29") (pintype "input"))
      (node (ref "COB_RIGHT2") (pin "3") (pintype "input"))
      (node (ref "COB_TOP1") (pin "1") (pintype "input"))
      (node (ref "COB_TOP1") (pin "13") (pintype "input"))
      (node (ref "COB_TOP1") (pin "14") (pintype "input"))
      (node (ref "COB_TOP1") (pin "23") (pintype "input"))
      (node (ref "COB_TOP1") (pin "24") (pintype "input"))
      (node (ref "COB_TOP1") (pin "4") (pintype "input"))
      (node (ref "COB_TOP2") (pin "1") (pintype "input"))
      (node (ref "COB_TOP2") (pin "17") (pintype "input"))
      (node (ref "COB_TOP2") (pin "29") (pintype "input"))
      (node (ref "COB_TOP2") (pin "3") (pintype "input"))
      (node (ref "COB_TOP2") (pin "30") (pintype "input"))
      (node (ref "COB_TOP2") (pin "31") (pintype "input"))
      (node (ref "COB_TOP2") (pin "4") (pintype "input"))
    )
    (net (code "200") (name "VDD") (class "Default")
      (node (ref "C1") (pin "1") (pinfunction "1_1") (pintype "passive"))
      (node (ref "C10") (pin "1") (pinfunction "1_1") (pintype "passive"))
      (node (ref "C11") (pin "1") (pinfunction "1_1") (pintype "passive"))
      (node (ref "C12") (pin "1") (pinfunction "1_1") (pintype "passive"))
      (node (ref "C13") (pin "1") (pinfunction "1_1") (pintype "passive"))
      (node (ref "C14") (pin "1") (pinfunction "1_1") (pintype "passive"))
      (node (ref "C15") (pin "1") (pinfunction "1_1") (pintype "passive"))
      (node (ref "C16") (pin "1") (pinfunction "1_1") (pintype "passive"))
      (node (ref "C17") (pin "1") (pinfunction "1_1") (pintype "passive"))
      (node (ref "C18") (pin "1") (pinfunction "1_1") (pintype "passive"))
      (node (ref "C19") (pin "1") (pinfunction "1_1") (pintype "passive"))
      (node (ref "C2") (pin "1") (pinfunction "1_1") (pintype "passive"))
      (node (ref "C20") (pin "1") (pinfunction "1_1") (pintype "passive"))
      (node (ref "C21") (pin "1") (pinfunction "1_1") (pintype "passive"))
      (node (ref "C22") (pin "1") (pinfunction "1_1") (pintype "passive"))
      (node (ref "C23") (pin "1") (pinfunction "1_1") (pintype "passive"))
      (node (ref "C24") (pin "1") (pinfunction "1_1") (pintype "passive"))
      (node (ref "C25") (pin "1") (pinfunction "1_1") (pintype "passive"))
      (node (ref "C26") (pin "1") (pinfunction "1_1") (pintype "passive"))
      (node (ref "C27") (pin "1") (pinfunction "1_1") (pintype "passive"))
      (node (ref "C28") (pin "1") (pinfunction "1_1") (pintype "passive"))
      (node (ref "C29") (pin "1") (pinfunction "1_1") (pintype "passive"))
      (node (ref "C3") (pin "1") (pinfunction "1_1") (pintype "passive"))
      (node (ref "C30") (pin "1") (pinfunction "1_1") (pintype "passive"))
      (node (ref "C4") (pin "1") (pinfunction "1_1") (pintype "passive"))
      (node (ref "C5") (pin "1") (pinfunction "1_1") (pintype "passive"))
      (node (ref "C6") (pin "1") (pinfunction "1_1") (pintype "passive"))
      (node (ref "C7") (pin "1") (pinfunction "1_1") (pintype "passive"))
      (node (ref "C8") (pin "1") (pinfunction "1_1") (pintype "passive"))
      (node (ref "C9") (pin "1") (pinfunction "1_1") (pintype "passive"))
      (node (ref "COB_BOTTOM1") (pin "2") (pintype "input"))
      (node (ref "COB_BOTTOM2") (pin "2") (pintype "input"))
      (node (ref "COB_BOTTOM2") (pin "32") (pintype "input"))
      (node (ref "COB_LEFT1") (pin "18") (pintype "input"))
      (node (ref "COB_LEFT1") (pin "4") (pintype "input"))
      (node (ref "COB_LEFT2") (pin "22") (pintype "input"))
      (node (ref "COB_LEFT2") (pin "4") (pintype "input"))
      (node (ref "COB_RIGHT1") (pin "22") (pintype "input"))
      (node (ref "COB_RIGHT1") (pin "8") (pintype "input"))
      (node (ref "COB_RIGHT2") (pin "16") (pintype "input"))
      (node (ref "COB_RIGHT2") (pin "30") (pintype "input"))
      (node (ref "COB_RIGHT2") (pin "4") (pintype "input"))
      (node (ref "COB_TOP1") (pin "2") (pintype "input"))
      (node (ref "COB_TOP2") (pin "2") (pintype "input"))
      (node (ref "COB_TOP2") (pin "32") (pintype "input"))
    )
  )
)
